# 18_Power_Management.net
KiCad netlist of a schematic drawn in Altium Designer
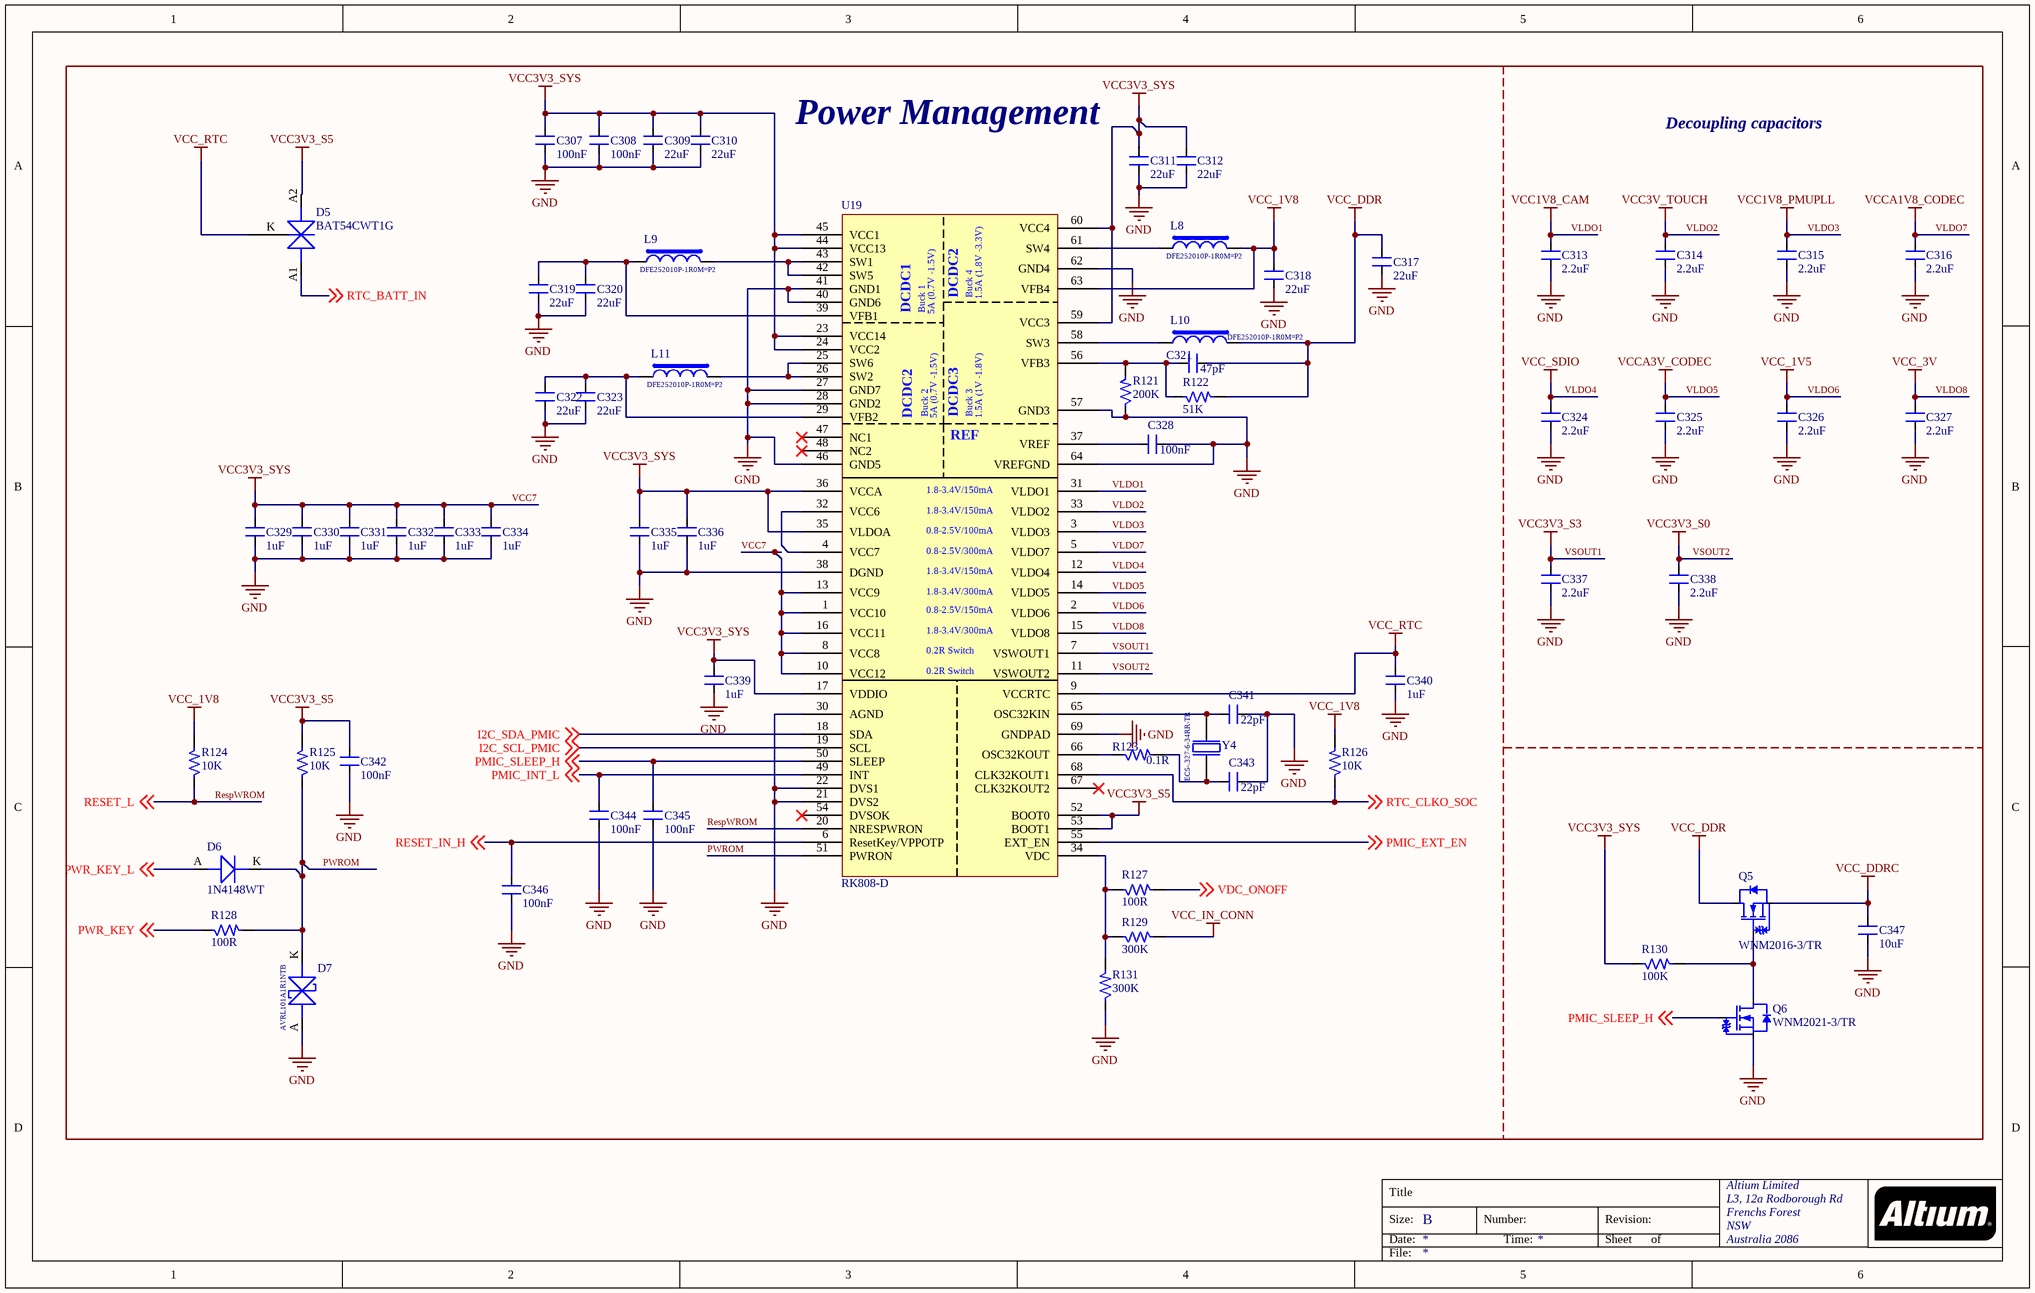
[diagram p0: [18] Power_Management.SchDoc]

(export (version "E")
  (design (tool "Eeschema 10.0.6"))
  (components
    (comp (ref "C307")
      (value "100nF")
      (footprint "CAP_0402")
      (description "0.1µF ±10% 25V Ceramic Capacitor X7R 0402 (1005 Metric)")
      (fields
        (field (name "MANUFACTURER") "Walsin Technology Corporation")
        (field (name "MANUFACTURER PART NUMBER") "0402B104K250CT")
      )
      (libsource (lib "EsteemPCB_SOM_Course_intlib") (part "CAP_100nF-25V-10%-0402"))
    )
    (comp (ref "C308")
      (value "100nF")
      (footprint "CAP_0402")
      (description "0.1µF ±10% 25V Ceramic Capacitor X7R 0402 (1005 Metric)")
      (fields
        (field (name "MANUFACTURER") "Walsin Technology Corporation")
        (field (name "MANUFACTURER PART NUMBER") "0402B104K250CT")
      )
      (libsource (lib "EsteemPCB_SOM_Course_intlib") (part "CAP_100nF-25V-10%-0402"))
    )
    (comp (ref "C309")
      (value "22uF")
      (footprint "CAP_0603")
      (description "22µF ±20% 10V Ceramic Capacitor X5R 0603 (1608 Metric)")
      (fields
        (field (name "MANUFACTURER") "Murata Electronics")
        (field (name "MANUFACTURER PART NUMBER") "GRM188R61A226ME15D")
      )
      (libsource (lib "EsteemPCB_SOM_Course_intlib") (part "CAP_22uF-10V-20%-0603"))
    )
    (comp (ref "C310")
      (value "22uF")
      (footprint "CAP_0603")
      (description "22µF ±20% 10V Ceramic Capacitor X5R 0603 (1608 Metric)")
      (fields
        (field (name "MANUFACTURER") "Murata Electronics")
        (field (name "MANUFACTURER PART NUMBER") "GRM188R61A226ME15D")
      )
      (libsource (lib "EsteemPCB_SOM_Course_intlib") (part "CAP_22uF-10V-20%-0603"))
    )
    (comp (ref "C311")
      (value "22uF")
      (footprint "CAP_0603")
      (description "22µF ±20% 10V Ceramic Capacitor X5R 0603 (1608 Metric)")
      (fields
        (field (name "MANUFACTURER") "Murata Electronics")
        (field (name "MANUFACTURER PART NUMBER") "GRM188R61A226ME15D")
      )
      (libsource (lib "EsteemPCB_SOM_Course_intlib") (part "CAP_22uF-10V-20%-0603"))
    )
    (comp (ref "C312")
      (value "22uF")
      (footprint "CAP_0603")
      (description "22µF ±20% 10V Ceramic Capacitor X5R 0603 (1608 Metric)")
      (fields
        (field (name "MANUFACTURER") "Murata Electronics")
        (field (name "MANUFACTURER PART NUMBER") "GRM188R61A226ME15D")
      )
      (libsource (lib "EsteemPCB_SOM_Course_intlib") (part "CAP_22uF-10V-20%-0603"))
    )
    (comp (ref "C313")
      (value "2.2uF")
      (footprint "CAP_0402")
      (description "2.2µF ±10% 10V Ceramic Capacitor X5R 0402 (1005 Metric)")
      (fields
        (field (name "MANUFACTURER") "Murata Electronics")
        (field (name "MANUFACTURER PART NUMBER") "GRM155R61A225KE95D")
      )
      (libsource (lib "EsteemPCB_SOM_Course_intlib") (part "CAP_2.2uF-10V-10%-0402"))
    )
    (comp (ref "C314")
      (value "2.2uF")
      (footprint "CAP_0402")
      (description "2.2µF ±10% 10V Ceramic Capacitor X5R 0402 (1005 Metric)")
      (fields
        (field (name "MANUFACTURER") "Murata Electronics")
        (field (name "MANUFACTURER PART NUMBER") "GRM155R61A225KE95D")
      )
      (libsource (lib "EsteemPCB_SOM_Course_intlib") (part "CAP_2.2uF-10V-10%-0402"))
    )
    (comp (ref "C315")
      (value "2.2uF")
      (footprint "CAP_0402")
      (description "2.2µF ±10% 10V Ceramic Capacitor X5R 0402 (1005 Metric)")
      (fields
        (field (name "MANUFACTURER") "Murata Electronics")
        (field (name "MANUFACTURER PART NUMBER") "GRM155R61A225KE95D")
      )
      (libsource (lib "EsteemPCB_SOM_Course_intlib") (part "CAP_2.2uF-10V-10%-0402"))
    )
    (comp (ref "C316")
      (value "2.2uF")
      (footprint "CAP_0402")
      (description "2.2µF ±10% 10V Ceramic Capacitor X5R 0402 (1005 Metric)")
      (fields
        (field (name "MANUFACTURER") "Murata Electronics")
        (field (name "MANUFACTURER PART NUMBER") "GRM155R61A225KE95D")
      )
      (libsource (lib "EsteemPCB_SOM_Course_intlib") (part "CAP_2.2uF-10V-10%-0402"))
    )
    (comp (ref "C317")
      (value "22uF")
      (footprint "CAP_0603")
      (description "22µF ±20% 10V Ceramic Capacitor X5R 0603 (1608 Metric)")
      (fields
        (field (name "MANUFACTURER") "Murata Electronics")
        (field (name "MANUFACTURER PART NUMBER") "GRM188R61A226ME15D")
      )
      (libsource (lib "EsteemPCB_SOM_Course_intlib") (part "CAP_22uF-10V-20%-0603"))
    )
    (comp (ref "C318")
      (value "22uF")
      (footprint "CAP_0603")
      (description "22µF ±20% 10V Ceramic Capacitor X5R 0603 (1608 Metric)")
      (fields
        (field (name "MANUFACTURER") "Murata Electronics")
        (field (name "MANUFACTURER PART NUMBER") "GRM188R61A226ME15D")
      )
      (libsource (lib "EsteemPCB_SOM_Course_intlib") (part "CAP_22uF-10V-20%-0603"))
    )
    (comp (ref "C319")
      (value "22uF")
      (footprint "CAP_0603")
      (description "22µF ±20% 10V Ceramic Capacitor X5R 0603 (1608 Metric)")
      (fields
        (field (name "MANUFACTURER") "Murata Electronics")
        (field (name "MANUFACTURER PART NUMBER") "GRM188R61A226ME15D")
      )
      (libsource (lib "EsteemPCB_SOM_Course_intlib") (part "CAP_22uF-10V-20%-0603"))
    )
    (comp (ref "C320")
      (value "22uF")
      (footprint "CAP_0603")
      (description "22µF ±20% 10V Ceramic Capacitor X5R 0603 (1608 Metric)")
      (fields
        (field (name "MANUFACTURER") "Murata Electronics")
        (field (name "MANUFACTURER PART NUMBER") "GRM188R61A226ME15D")
      )
      (libsource (lib "EsteemPCB_SOM_Course_intlib") (part "CAP_22uF-10V-20%-0603"))
    )
    (comp (ref "C321")
      (value "47pF")
      (footprint "CAP_0402")
      (description "47pF ±10% 10V Ceramic Capacitor C0G, NP0 0402 (1005 Metric)")
      (fields
        (field (name "MANUFACTURER") "KEMET")
        (field (name "MANUFACTURER PART NUMBER") "C0402C470K8GAC7867")
      )
      (libsource (lib "EsteemPCB_SOM_Course_intlib") (part "CAP_47pF-10V-10%-0402"))
    )
    (comp (ref "C322")
      (value "22uF")
      (footprint "CAP_0603")
      (description "22µF ±20% 10V Ceramic Capacitor X5R 0603 (1608 Metric)")
      (fields
        (field (name "MANUFACTURER") "Murata Electronics")
        (field (name "MANUFACTURER PART NUMBER") "GRM188R61A226ME15D")
      )
      (libsource (lib "EsteemPCB_SOM_Course_intlib") (part "CAP_22uF-10V-20%-0603"))
    )
    (comp (ref "C323")
      (value "22uF")
      (footprint "CAP_0603")
      (description "22µF ±20% 10V Ceramic Capacitor X5R 0603 (1608 Metric)")
      (fields
        (field (name "MANUFACTURER") "Murata Electronics")
        (field (name "MANUFACTURER PART NUMBER") "GRM188R61A226ME15D")
      )
      (libsource (lib "EsteemPCB_SOM_Course_intlib") (part "CAP_22uF-10V-20%-0603"))
    )
    (comp (ref "C324")
      (value "2.2uF")
      (footprint "CAP_0402")
      (description "2.2µF ±10% 10V Ceramic Capacitor X5R 0402 (1005 Metric)")
      (fields
        (field (name "MANUFACTURER") "Murata Electronics")
        (field (name "MANUFACTURER PART NUMBER") "GRM155R61A225KE95D")
      )
      (libsource (lib "EsteemPCB_SOM_Course_intlib") (part "CAP_2.2uF-10V-10%-0402"))
    )
    (comp (ref "C325")
      (value "2.2uF")
      (footprint "CAP_0402")
      (description "2.2µF ±10% 10V Ceramic Capacitor X5R 0402 (1005 Metric)")
      (fields
        (field (name "MANUFACTURER") "Murata Electronics")
        (field (name "MANUFACTURER PART NUMBER") "GRM155R61A225KE95D")
      )
      (libsource (lib "EsteemPCB_SOM_Course_intlib") (part "CAP_2.2uF-10V-10%-0402"))
    )
    (comp (ref "C326")
      (value "2.2uF")
      (footprint "CAP_0402")
      (description "2.2µF ±10% 10V Ceramic Capacitor X5R 0402 (1005 Metric)")
      (fields
        (field (name "MANUFACTURER") "Murata Electronics")
        (field (name "MANUFACTURER PART NUMBER") "GRM155R61A225KE95D")
      )
      (libsource (lib "EsteemPCB_SOM_Course_intlib") (part "CAP_2.2uF-10V-10%-0402"))
    )
    (comp (ref "C327")
      (value "2.2uF")
      (footprint "CAP_0402")
      (description "2.2µF ±10% 10V Ceramic Capacitor X5R 0402 (1005 Metric)")
      (fields
        (field (name "MANUFACTURER") "Murata Electronics")
        (field (name "MANUFACTURER PART NUMBER") "GRM155R61A225KE95D")
      )
      (libsource (lib "EsteemPCB_SOM_Course_intlib") (part "CAP_2.2uF-10V-10%-0402"))
    )
    (comp (ref "C328")
      (value "100nF")
      (footprint "CAP_0402")
      (description "0.1µF ±10% 10V Ceramic Capacitor X7R 0402 (1005 Metric)")
      (fields
        (field (name "MANUFACTURER") "Yageo")
        (field (name "MANUFACTURER PART NUMBER") "CC0402KRX7R6BB104")
      )
      (libsource (lib "EsteemPCB_SOM_Course_intlib") (part "CAP_100nF-10V-10%-0402"))
    )
    (comp (ref "C329")
      (value "1uF")
      (footprint "CAP_0402")
      (description "1µF ±10% 10V Ceramic Capacitor X6S 0402 (1005 Metric)")
      (fields
        (field (name "MANUFACTURER") "Murata Electronics")
        (field (name "MANUFACTURER PART NUMBER") "GRT155C81A105KE01D")
      )
      (libsource (lib "EsteemPCB_SOM_Course_intlib") (part "CAP_1uF-10V-10%-0402"))
    )
    (comp (ref "C330")
      (value "1uF")
      (footprint "CAP_0402")
      (description "1µF ±10% 10V Ceramic Capacitor X6S 0402 (1005 Metric)")
      (fields
        (field (name "MANUFACTURER") "Murata Electronics")
        (field (name "MANUFACTURER PART NUMBER") "GRT155C81A105KE01D")
      )
      (libsource (lib "EsteemPCB_SOM_Course_intlib") (part "CAP_1uF-10V-10%-0402"))
    )
    (comp (ref "C331")
      (value "1uF")
      (footprint "CAP_0402")
      (description "1µF ±10% 10V Ceramic Capacitor X6S 0402 (1005 Metric)")
      (fields
        (field (name "MANUFACTURER") "Murata Electronics")
        (field (name "MANUFACTURER PART NUMBER") "GRT155C81A105KE01D")
      )
      (libsource (lib "EsteemPCB_SOM_Course_intlib") (part "CAP_1uF-10V-10%-0402"))
    )
    (comp (ref "C332")
      (value "1uF")
      (footprint "CAP_0402")
      (description "1µF ±10% 10V Ceramic Capacitor X6S 0402 (1005 Metric)")
      (fields
        (field (name "MANUFACTURER") "Murata Electronics")
        (field (name "MANUFACTURER PART NUMBER") "GRT155C81A105KE01D")
      )
      (libsource (lib "EsteemPCB_SOM_Course_intlib") (part "CAP_1uF-10V-10%-0402"))
    )
    (comp (ref "C333")
      (value "1uF")
      (footprint "CAP_0402")
      (description "1µF ±10% 10V Ceramic Capacitor X6S 0402 (1005 Metric)")
      (fields
        (field (name "MANUFACTURER") "Murata Electronics")
        (field (name "MANUFACTURER PART NUMBER") "GRT155C81A105KE01D")
      )
      (libsource (lib "EsteemPCB_SOM_Course_intlib") (part "CAP_1uF-10V-10%-0402"))
    )
    (comp (ref "C334")
      (value "1uF")
      (footprint "CAP_0402")
      (description "1µF ±10% 10V Ceramic Capacitor X6S 0402 (1005 Metric)")
      (fields
        (field (name "MANUFACTURER") "Murata Electronics")
        (field (name "MANUFACTURER PART NUMBER") "GRT155C81A105KE01D")
      )
      (libsource (lib "EsteemPCB_SOM_Course_intlib") (part "CAP_1uF-10V-10%-0402"))
    )
    (comp (ref "C335")
      (value "1uF")
      (footprint "CAP_0402")
      (description "1µF ±10% 10V Ceramic Capacitor X6S 0402 (1005 Metric)")
      (fields
        (field (name "MANUFACTURER") "Murata Electronics")
        (field (name "MANUFACTURER PART NUMBER") "GRT155C81A105KE01D")
      )
      (libsource (lib "EsteemPCB_SOM_Course_intlib") (part "CAP_1uF-10V-10%-0402"))
    )
    (comp (ref "C336")
      (value "1uF")
      (footprint "CAP_0402")
      (description "1µF ±10% 10V Ceramic Capacitor X6S 0402 (1005 Metric)")
      (fields
        (field (name "MANUFACTURER") "Murata Electronics")
        (field (name "MANUFACTURER PART NUMBER") "GRT155C81A105KE01D")
      )
      (libsource (lib "EsteemPCB_SOM_Course_intlib") (part "CAP_1uF-10V-10%-0402"))
    )
    (comp (ref "C337")
      (value "2.2uF")
      (footprint "CAP_0402")
      (description "2.2µF ±10% 10V Ceramic Capacitor X5R 0402 (1005 Metric)")
      (fields
        (field (name "MANUFACTURER") "Murata Electronics")
        (field (name "MANUFACTURER PART NUMBER") "GRM155R61A225KE95D")
      )
      (libsource (lib "EsteemPCB_SOM_Course_intlib") (part "CAP_2.2uF-10V-10%-0402"))
    )
    (comp (ref "C338")
      (value "2.2uF")
      (footprint "CAP_0402")
      (description "2.2µF ±10% 10V Ceramic Capacitor X5R 0402 (1005 Metric)")
      (fields
        (field (name "MANUFACTURER") "Murata Electronics")
        (field (name "MANUFACTURER PART NUMBER") "GRM155R61A225KE95D")
      )
      (libsource (lib "EsteemPCB_SOM_Course_intlib") (part "CAP_2.2uF-10V-10%-0402"))
    )
    (comp (ref "C339")
      (value "1uF")
      (footprint "CAP_0402")
      (description "1µF ±10% 10V Ceramic Capacitor X6S 0402 (1005 Metric)")
      (fields
        (field (name "MANUFACTURER") "Murata Electronics")
        (field (name "MANUFACTURER PART NUMBER") "GRT155C81A105KE01D")
      )
      (libsource (lib "EsteemPCB_SOM_Course_intlib") (part "CAP_1uF-10V-10%-0402"))
    )
    (comp (ref "C340")
      (value "1uF")
      (footprint "CAP_0402")
      (description "1µF ±10% 16V Ceramic Capacitor X5R 0402 (1005 Metric)")
      (fields
        (field (name "MANUFACTURER") "Knowles Novacap")
        (field (name "MANUFACTURER PART NUMBER") "0402BW105K160YT")
      )
      (libsource (lib "EsteemPCB_SOM_Course_intlib") (part "CAP_1uF-16V-10%-0402"))
    )
    (comp (ref "C341")
      (value "22pF")
      (footprint "CAP_0402")
      (description "22pF ±10% 10V Ceramic Capacitor C0G, NP0 0402 (1005 Metric)")
      (fields
        (field (name "MANUFACTURER") "KEMET")
        (field (name "MANUFACTURER PART NUMBER") "C0402C220K8GACTU")
      )
      (libsource (lib "EsteemPCB_SOM_Course_intlib") (part "CAP_22pF-10V-10%-0402"))
    )
    (comp (ref "C342")
      (value "100nF")
      (footprint "CAP_0402")
      (description "0.1µF ±10% 10V Ceramic Capacitor X7R 0402 (1005 Metric)")
      (fields
        (field (name "MANUFACTURER") "Yageo")
        (field (name "MANUFACTURER PART NUMBER") "CC0402KRX7R6BB104")
      )
      (libsource (lib "EsteemPCB_SOM_Course_intlib") (part "CAP_100nF-10V-10%-0402"))
    )
    (comp (ref "C343")
      (value "22pF")
      (footprint "CAP_0402")
      (description "22pF ±10% 10V Ceramic Capacitor C0G, NP0 0402 (1005 Metric)")
      (fields
        (field (name "MANUFACTURER") "KEMET")
        (field (name "MANUFACTURER PART NUMBER") "C0402C220K8GACTU")
      )
      (libsource (lib "EsteemPCB_SOM_Course_intlib") (part "CAP_22pF-10V-10%-0402"))
    )
    (comp (ref "C344")
      (value "100nF")
      (footprint "CAP_0402")
      (description "0.1µF ±10% 10V Ceramic Capacitor X7R 0402 (1005 Metric)")
      (fields
        (field (name "MANUFACTURER") "Yageo")
        (field (name "MANUFACTURER PART NUMBER") "CC0402KRX7R6BB104")
      )
      (libsource (lib "EsteemPCB_SOM_Course_intlib") (part "CAP_100nF-10V-10%-0402"))
    )
    (comp (ref "C345")
      (value "100nF")
      (footprint "CAP_0402")
      (description "0.1µF ±10% 10V Ceramic Capacitor X7R 0402 (1005 Metric)")
      (fields
        (field (name "MANUFACTURER") "Yageo")
        (field (name "MANUFACTURER PART NUMBER") "CC0402KRX7R6BB104")
      )
      (libsource (lib "EsteemPCB_SOM_Course_intlib") (part "CAP_100nF-10V-10%-0402"))
    )
    (comp (ref "C346")
      (value "100nF")
      (footprint "CAP_0402")
      (description "0.1µF ±10% 10V Ceramic Capacitor X7R 0402 (1005 Metric)")
      (fields
        (field (name "MANUFACTURER") "Yageo")
        (field (name "MANUFACTURER PART NUMBER") "CC0402KRX7R6BB104")
      )
      (libsource (lib "EsteemPCB_SOM_Course_intlib") (part "CAP_100nF-10V-10%-0402"))
    )
    (comp (ref "C347")
      (value "10uF")
      (footprint "CAP_0402")
      (description "10µF ±20% 10V Ceramic Capacitor X5R 0402 (1005 Metric)")
      (fields
        (field (name "MANUFACTURER PART NUMBER") "CL05A106MP5NUNC")
        (field (name "MANUFACTURER") "Samsung Electro-Mechanics")
      )
      (libsource (lib "EsteemPCB_SOM_Course_intlib") (part "CAP_10uF-10V-20%-0402"))
    )
    (comp (ref "D5")
      (value "BAT54CWT1G")
      (footprint "DIO_SOT-323-3")
      (description "Diode Array 1 Pair Common Cathode Schottky 30V 200mA (DC) Surface Mount SC-70, SOT-323")
      (fields (field (name "MANUFACTURER") "ON Semiconductor"))
      (libsource (lib "EsteemPCB_SOM_Course_intlib") (part "DIO-S-A_30V-200mA-SOT-323"))
    )
    (comp (ref "D6")
      (value "1N4148WT")
      (footprint "DIO_SOD523")
      (description "Diode Standard 100V 300mA (DC) Surface Mount SOD-123")
      (fields (field (name "MANUFACTURER") "FAIRCHILD"))
      (libsource (lib "EsteemPCB_SOM_Course_intlib") (part "DIO_75V-200mA-SOD-523F"))
    )
    (comp (ref "D7")
      (value "AVRL101A1R1NTB")
      (footprint "DIO_0402_SMD")
      (description "39V Varistor 1 Circuit Surface Mount, MLCV 0402 (1005 Metric)")
      (fields (field (name "MANUFACTURER") "TDK Corporation"))
      (libsource (lib "EsteemPCB_SOM_Course_intlib") (part "DIO-T_10V-39V-0402"))
    )
    (comp (ref "L8")
      (value "DFE252010P-1R0M=P2")
      (footprint "IND_1008")
      (description "1µH Shielded Wirewound Inductor 3.8A 54mOhm Max 1008 (2520 Metric)")
      (fields (field (name "MANUFACTURER") "Murata Electronics"))
      (libsource (lib "EsteemPCB_SOM_Course_intlib") (part "IND_1uH-3.8A-20%-1008"))
    )
    (comp (ref "L9")
      (value "DFE252010P-1R0M=P2")
      (footprint "IND_1008")
      (description "1µH Shielded Wirewound Inductor 3.8A 54mOhm Max 1008 (2520 Metric)")
      (fields (field (name "MANUFACTURER") "Murata Electronics"))
      (libsource (lib "EsteemPCB_SOM_Course_intlib") (part "IND_1uH-3.8A-20%-1008"))
    )
    (comp (ref "L10")
      (value "DFE252010P-1R0M=P2")
      (footprint "IND_1008")
      (description "1µH Shielded Wirewound Inductor 3.8A 54mOhm Max 1008 (2520 Metric)")
      (fields (field (name "MANUFACTURER") "Murata Electronics"))
      (libsource (lib "EsteemPCB_SOM_Course_intlib") (part "IND_1uH-3.8A-20%-1008"))
    )
    (comp (ref "L11")
      (value "DFE252010P-1R0M=P2")
      (footprint "IND_1008")
      (description "1µH Shielded Wirewound Inductor 3.8A 54mOhm Max 1008 (2520 Metric)")
      (fields (field (name "MANUFACTURER") "Murata Electronics"))
      (libsource (lib "EsteemPCB_SOM_Course_intlib") (part "IND_1uH-3.8A-20%-1008"))
    )
    (comp (ref "Q5")
      (value "WNM2016-3/TR")
      (footprint "SOT 23-3")
      (description "N Channel 20V 2.9A 1V @ 250uA 47mΩ @ 3.6A,4.5V 700mW SOT-23(SOT-23-3) MOSFET RoHS")
      (fields (field (name "MANUFACTURER") "WILLSEMI(Will Semicon)"))
      (libsource (lib "EsteemPCB_SOM_Course_intlib") (part "MOSFET-N_20V-2.9A-SOT-23"))
    )
    (comp (ref "Q6")
      (value "WNM2021-3/TR")
      (footprint "SOT-323-3")
      (description "N Channel 20V 820mA 850mV @ 250uA 310mΩ @ 550mA,4.5V 310mW SOT-323(SC-70) MOSFET RoHS")
      (fields (field (name "MANUFACTURER") "WILLSEMI(Will Semicon)"))
      (libsource (lib "EsteemPCB_SOM_Course_intlib") (part "MOSFET-N_20V-820mA-SOT-323"))
    )
    (comp (ref "R121")
      (value "200K")
      (footprint "RES_0402")
      (description "200 kOhms ±1% 0.1W, 1/10W Chip Resistor 0402 (1005 Metric) Automotive AEC-Q200 Thick Film")
      (fields
        (field (name "MANUFACTURER") "Panasonic Electronic Components")
        (field (name "MANUFACTURER PART NUMBER") "ERJ-2RKF2003X")
      )
      (libsource (lib "EsteemPCB_SOM_Course_intlib") (part "RES_200K-0.1W-1%-0402"))
    )
    (comp (ref "R122")
      (value "51K")
      (footprint "RES_0402")
      (description "51 kOhms ±1% 0.1W, 1/10W Chip Resistor 0402 (1005 Metric) Automotive AEC-Q200 Thick Film")
      (fields
        (field (name "MANUFACTURER") "Panasonic Electronic Components")
        (field (name "MANUFACTURER PART NUMBER") "ERJ-2RKF5102X")
      )
      (libsource (lib "EsteemPCB_SOM_Course_intlib") (part "RES_51K-0.1W-1%-0402"))
    )
    (comp (ref "R123")
      (value "0.1R")
      (footprint "RES_0402")
      (fields
        (field (name "MANUFACTURER") "Samsung Electro-Mechanics")
        (field (name "MANUFACTURER PART NUMBER") "RUT1005FR100CS")
      )
      (libsource (lib "EsteemPCB_SOM_Course_intlib") (part "RES_0.1R-0.1W-1%-0402"))
    )
    (comp (ref "R124")
      (value "10K")
      (footprint "RES_0402")
      (description "10 kOhms ±1% 0.1W, 1/10W Chip Resistor 0402 (1005 Metric) Anti-Sulfur Thin Film")
      (fields
        (field (name "MANUFACTURER") "Vishay Beyschlag/Draloric/BC Components")
        (field (name "MANUFACTURER PART NUMBER") "MCS04020C1002FE000")
      )
      (libsource (lib "EsteemPCB_SOM_Course_intlib") (part "RES_10K-0.1W-1%-0402"))
    )
    (comp (ref "R125")
      (value "10K")
      (footprint "RES_0402")
      (description "10 kOhms ±1% 0.1W, 1/10W Chip Resistor 0402 (1005 Metric) Anti-Sulfur Thin Film")
      (fields
        (field (name "MANUFACTURER") "Vishay Beyschlag/Draloric/BC Components")
        (field (name "MANUFACTURER PART NUMBER") "MCS04020C1002FE000")
      )
      (libsource (lib "EsteemPCB_SOM_Course_intlib") (part "RES_10K-0.1W-1%-0402"))
    )
    (comp (ref "R126")
      (value "10K")
      (footprint "RES_0402")
      (description "10 kOhms ±1% 0.1W, 1/10W Chip Resistor 0402 (1005 Metric) Anti-Sulfur Thin Film")
      (fields
        (field (name "MANUFACTURER") "Vishay Beyschlag/Draloric/BC Components")
        (field (name "MANUFACTURER PART NUMBER") "MCS04020C1002FE000")
      )
      (libsource (lib "EsteemPCB_SOM_Course_intlib") (part "RES_10K-0.1W-1%-0402"))
    )
    (comp (ref "R127")
      (value "100R")
      (footprint "RES_0402")
      (fields
        (field (name "MANUFACTURER") "KOA Speer Electronics, Inc.")
        (field (name "MANUFACTURER PART NUMBER") "RK73H1ETTP1000F")
      )
      (libsource (lib "EsteemPCB_SOM_Course_intlib") (part "RES_100R-0.1W-1%-0402"))
    )
    (comp (ref "R128")
      (value "100R")
      (footprint "RES_0402")
      (fields
        (field (name "MANUFACTURER") "KOA Speer Electronics, Inc.")
        (field (name "MANUFACTURER PART NUMBER") "RK73H1ETTP1000F")
      )
      (libsource (lib "EsteemPCB_SOM_Course_intlib") (part "RES_100R-0.1W-1%-0402"))
    )
    (comp (ref "R129")
      (value "300K")
      (footprint "RES_0402")
      (description "300 kOhms ±1% 0.1W, 1/10W Chip Resistor 0402 (1005 Metric) Automotive AEC-Q200 Thick Film")
      (fields
        (field (name "MANUFACTURER") "Panasonic Electronic Components")
        (field (name "MANUFACTURER PART NUMBER") "ERJ-2RKF3003X")
      )
      (libsource (lib "EsteemPCB_SOM_Course_intlib") (part "RES_300K-0.1W-1%-0402"))
    )
    (comp (ref "R130")
      (value "100K")
      (footprint "RES_0402")
      (description "100 kOhms ±1% 0.1W, 1/10W Chip Resistor 0402 (1005 Metric) Anti-Sulfur Thin Film")
      (fields
        (field (name "MANUFACTURER") "Vishay Beyschlag/Draloric/BC Components")
        (field (name "MANUFACTURER PART NUMBER") "MCS04020C1003FE000")
      )
      (libsource (lib "EsteemPCB_SOM_Course_intlib") (part "RES_100K-0.1W-1%-0402"))
    )
    (comp (ref "R131")
      (value "300K")
      (footprint "RES_0402")
      (description "300 kOhms ±1% 0.1W, 1/10W Chip Resistor 0402 (1005 Metric) Automotive AEC-Q200 Thick Film")
      (fields
        (field (name "MANUFACTURER") "Panasonic Electronic Components")
        (field (name "MANUFACTURER PART NUMBER") "ERJ-2RKF3003X")
      )
      (libsource (lib "EsteemPCB_SOM_Course_intlib") (part "RES_300K-0.1W-1%-0402"))
    )
    (comp (ref "U19")
      (value "RK808-D")
      (footprint "QFN68_13.7_220.4X220.4_SMD")
      (description "The RK808 is a complete power supply solution for Portable systems.")
      (fields (field (name "MANUFACTURER") "Rockchip"))
      (libsource (lib "EsteemPCB_SOM_Course_intlib") (part "IC_RK808-D-QFN68"))
    )
    (comp (ref "Y4")
      (value "ECS-.327-6-34RR-TR")
      (footprint "XTAL_ECS-.327-6-34RR-TR")
      (description "32.768kHz ±20ppm Crystal 12pF 80 kOhms 2-SMD, No Lead")
      (fields (field (name "MANUFACTURER") "Ecliptek"))
      (libsource (lib "EsteemPCB_SOM_Course_intlib") (part "XTAL_32.768Khz-22pF-SMD"))
    )
  )
  (nets
    (net (code "1") (name "/PWROM") (class "Default")
      (node (ref "D6") (pin "K") (pinfunction "CATHODE_K") (pintype "passive"))
      (node (ref "D7") (pin "K") (pinfunction "K_K") (pintype "passive"))
      (node (ref "R125") (pin "1") (pinfunction "1_1") (pintype "passive"))
      (node (ref "R128") (pin "2") (pinfunction "2_2") (pintype "passive"))
      (node (ref "U19") (pin "51") (pinfunction "PWRON_51") (pintype "passive"))
    )
    (net (code "2") (name "GND") (class "Default")
      (node (ref "C307") (pin "1") (pinfunction "1_1") (pintype "passive"))
      (node (ref "C308") (pin "1") (pinfunction "1_1") (pintype "passive"))
      (node (ref "C309") (pin "1") (pinfunction "1_1") (pintype "passive"))
      (node (ref "C310") (pin "1") (pinfunction "1_1") (pintype "passive"))
      (node (ref "C311") (pin "1") (pinfunction "1_1") (pintype "passive"))
      (node (ref "C312") (pin "1") (pinfunction "1_1") (pintype "passive"))
      (node (ref "C313") (pin "1") (pinfunction "1_1") (pintype "passive"))
      (node (ref "C314") (pin "1") (pinfunction "1_1") (pintype "passive"))
      (node (ref "C315") (pin "1") (pinfunction "1_1") (pintype "passive"))
      (node (ref "C316") (pin "1") (pinfunction "1_1") (pintype "passive"))
      (node (ref "C317") (pin "1") (pinfunction "1_1") (pintype "passive"))
      (node (ref "C318") (pin "1") (pinfunction "1_1") (pintype "passive"))
      (node (ref "C319") (pin "1") (pinfunction "1_1") (pintype "passive"))
      (node (ref "C320") (pin "1") (pinfunction "1_1") (pintype "passive"))
      (node (ref "C322") (pin "1") (pinfunction "1_1") (pintype "passive"))
      (node (ref "C323") (pin "1") (pinfunction "1_1") (pintype "passive"))
      (node (ref "C324") (pin "1") (pinfunction "1_1") (pintype "passive"))
      (node (ref "C325") (pin "1") (pinfunction "1_1") (pintype "passive"))
      (node (ref "C326") (pin "1") (pinfunction "1_1") (pintype "passive"))
      (node (ref "C327") (pin "1") (pinfunction "1_1") (pintype "passive"))
      (node (ref "C328") (pin "2") (pinfunction "2_2") (pintype "passive"))
      (node (ref "C329") (pin "1") (pinfunction "1_1") (pintype "passive"))
      (node (ref "C330") (pin "1") (pinfunction "1_1") (pintype "passive"))
      (node (ref "C331") (pin "1") (pinfunction "1_1") (pintype "passive"))
      (node (ref "C332") (pin "1") (pinfunction "1_1") (pintype "passive"))
      (node (ref "C333") (pin "1") (pinfunction "1_1") (pintype "passive"))
      (node (ref "C334") (pin "1") (pinfunction "1_1") (pintype "passive"))
      (node (ref "C335") (pin "1") (pinfunction "1_1") (pintype "passive"))
      (node (ref "C336") (pin "1") (pinfunction "1_1") (pintype "passive"))
      (node (ref "C337") (pin "1") (pinfunction "1_1") (pintype "passive"))
      (node (ref "C338") (pin "1") (pinfunction "1_1") (pintype "passive"))
      (node (ref "C339") (pin "1") (pinfunction "1_1") (pintype "passive"))
      (node (ref "C340") (pin "1") (pinfunction "1_1") (pintype "passive"))
      (node (ref "C341") (pin "2") (pinfunction "2_2") (pintype "passive"))
      (node (ref "C342") (pin "1") (pinfunction "1_1") (pintype "passive"))
      (node (ref "C343") (pin "2") (pinfunction "2_2") (pintype "passive"))
      (node (ref "C344") (pin "1") (pinfunction "1_1") (pintype "passive"))
      (node (ref "C345") (pin "1") (pinfunction "1_1") (pintype "passive"))
      (node (ref "C346") (pin "1") (pinfunction "1_1") (pintype "passive"))
      (node (ref "C347") (pin "1") (pinfunction "1_1") (pintype "passive"))
      (node (ref "D7") (pin "A") (pinfunction "A_A") (pintype "passive"))
      (node (ref "Q6") (pin "2") (pinfunction "S_2") (pintype "passive"))
      (node (ref "R121") (pin "1") (pinfunction "1_1") (pintype "passive"))
      (node (ref "R131") (pin "1") (pinfunction "1_1") (pintype "passive"))
      (node (ref "U19") (pin "21") (pinfunction "DVS2_21") (pintype "passive"))
      (node (ref "U19") (pin "22") (pinfunction "DVS1_22") (pintype "passive"))
      (node (ref "U19") (pin "27") (pinfunction "GND7_27") (pintype "passive"))
      (node (ref "U19") (pin "28") (pinfunction "GND2_28") (pintype "passive"))
      (node (ref "U19") (pin "30") (pinfunction "AGND_30") (pintype "passive"))
      (node (ref "U19") (pin "38") (pinfunction "DGND_38") (pintype "passive"))
      (node (ref "U19") (pin "40") (pinfunction "GND6_40") (pintype "passive"))
      (node (ref "U19") (pin "41") (pinfunction "GND1_41") (pintype "passive"))
      (node (ref "U19") (pin "46") (pinfunction "GND5_46") (pintype "passive"))
      (node (ref "U19") (pin "57") (pinfunction "GND3_57") (pintype "passive"))
      (node (ref "U19") (pin "62") (pinfunction "GND4_62") (pintype "passive"))
      (node (ref "U19") (pin "64") (pinfunction "VREFGND_64") (pintype "passive"))
      (node (ref "U19") (pin "69") (pinfunction "GNDPAD_69") (pintype "passive"))
    )
    (net (code "3") (name "I2C_SCL_PMIC") (class "Default")
      (node (ref "U19") (pin "19") (pinfunction "SCL_19") (pintype "passive"))
    )
    (net (code "4") (name "I2C_SDA_PMIC") (class "Default")
      (node (ref "U19") (pin "18") (pinfunction "SDA_18") (pintype "passive"))
    )
    (net (code "5") (name "Net-(C343-Pad1)") (class "Default")
      (node (ref "C343") (pin "1") (pinfunction "1_1") (pintype "passive"))
      (node (ref "R123") (pin "2") (pinfunction "2_2") (pintype "passive"))
      (node (ref "Y4") (pin "1") (pinfunction "1_1") (pintype "passive"))
    )
    (net (code "6") (name "Net-(Q5-G)") (class "Default")
      (node (ref "Q5") (pin "1") (pinfunction "G_1") (pintype "passive"))
      (node (ref "Q6") (pin "3") (pinfunction "D_3") (pintype "passive"))
      (node (ref "R130") (pin "2") (pinfunction "2_2") (pintype "passive"))
    )
    (net (code "7") (name "Net-(U19-OSC32KIN)") (class "Default")
      (node (ref "C341") (pin "1") (pinfunction "1_1") (pintype "passive"))
      (node (ref "U19") (pin "65") (pinfunction "OSC32KIN_65") (pintype "passive"))
      (node (ref "Y4") (pin "2") (pinfunction "2_2") (pintype "passive"))
    )
    (net (code "8") (name "Net-(U19-OSC32KOUT)") (class "Default")
      (node (ref "R123") (pin "1") (pinfunction "1_1") (pintype "passive"))
      (node (ref "U19") (pin "66") (pinfunction "OSC32KOUT_66") (pintype "passive"))
    )
    (net (code "9") (name "Net-(U19-SW1)") (class "Default")
      (node (ref "L9") (pin "2") (pinfunction "2_2") (pintype "passive"))
      (node (ref "U19") (pin "42") (pinfunction "SW5_42") (pintype "passive"))
      (node (ref "U19") (pin "43") (pinfunction "SW1_43") (pintype "passive"))
    )
    (net (code "10") (name "Net-(U19-SW2)") (class "Default")
      (node (ref "L11") (pin "2") (pinfunction "2_2") (pintype "passive"))
      (node (ref "U19") (pin "25") (pinfunction "SW6_25") (pintype "passive"))
      (node (ref "U19") (pin "26") (pinfunction "SW2_26") (pintype "passive"))
    )
    (net (code "11") (name "Net-(U19-SW3)") (class "Default")
      (node (ref "L10") (pin "1") (pinfunction "1_1") (pintype "passive"))
      (node (ref "U19") (pin "58") (pinfunction "SW3_58") (pintype "passive"))
    )
    (net (code "12") (name "Net-(U19-SW4)") (class "Default")
      (node (ref "L8") (pin "1") (pinfunction "1_1") (pintype "passive"))
      (node (ref "U19") (pin "61") (pinfunction "SW4_61") (pintype "passive"))
    )
    (net (code "13") (name "Net-(U19-VCC6)") (class "Default")
      (node (ref "U19") (pin "32") (pinfunction "VCC6_32") (pintype "passive"))
      (node (ref "U19") (pin "4") (pinfunction "VCC7_4") (pintype "passive"))
    )
    (net (code "14") (name "Net-(U19-VDC)") (class "Default")
      (node (ref "R127") (pin "1") (pinfunction "1_1") (pintype "passive"))
      (node (ref "R129") (pin "1") (pinfunction "1_1") (pintype "passive"))
      (node (ref "R131") (pin "2") (pinfunction "2_2") (pintype "passive"))
      (node (ref "U19") (pin "34") (pinfunction "VDC_34") (pintype "passive"))
    )
    (net (code "15") (name "Net-(U19-VFB1)") (class "Default")
      (node (ref "C319") (pin "2") (pinfunction "2_2") (pintype "passive"))
      (node (ref "C320") (pin "2") (pinfunction "2_2") (pintype "passive"))
      (node (ref "L9") (pin "1") (pinfunction "1_1") (pintype "passive"))
      (node (ref "U19") (pin "39") (pinfunction "VFB1_39") (pintype "passive"))
    )
    (net (code "16") (name "Net-(U19-VFB2)") (class "Default")
      (node (ref "C322") (pin "2") (pinfunction "2_2") (pintype "passive"))
      (node (ref "C323") (pin "2") (pinfunction "2_2") (pintype "passive"))
      (node (ref "L11") (pin "1") (pinfunction "1_1") (pintype "passive"))
      (node (ref "U19") (pin "29") (pinfunction "VFB2_29") (pintype "passive"))
    )
    (net (code "17") (name "Net-(U19-VFB3)") (class "Default")
      (node (ref "C321") (pin "1") (pinfunction "1_1") (pintype "passive"))
      (node (ref "R121") (pin "2") (pinfunction "2_2") (pintype "passive"))
      (node (ref "R122") (pin "1") (pinfunction "1_1") (pintype "passive"))
      (node (ref "U19") (pin "56") (pinfunction "VFB3_56") (pintype "passive"))
    )
    (net (code "18") (name "Net-(U19-VREF)") (class "Default")
      (node (ref "C328") (pin "1") (pinfunction "1_1") (pintype "passive"))
      (node (ref "U19") (pin "37") (pinfunction "VREF_37") (pintype "passive"))
    )
    (net (code "19") (name "PMIC_EXT_EN") (class "Default")
      (node (ref "U19") (pin "55") (pinfunction "EXT_EN_55") (pintype "passive"))
    )
    (net (code "20") (name "PMIC_INT_L") (class "Default")
      (node (ref "C344") (pin "2") (pinfunction "2_2") (pintype "passive"))
      (node (ref "U19") (pin "49") (pinfunction "INT_49") (pintype "passive"))
    )
    (net (code "21") (name "PMIC_SLEEP_H") (class "Default")
      (node (ref "C345") (pin "2") (pinfunction "2_2") (pintype "passive"))
      (node (ref "Q6") (pin "1") (pinfunction "G_1") (pintype "passive"))
      (node (ref "U19") (pin "50") (pinfunction "SLEEP_50") (pintype "passive"))
    )
    (net (code "22") (name "PWR_KEY") (class "Default")
      (node (ref "R128") (pin "1") (pinfunction "1_1") (pintype "passive"))
    )
    (net (code "23") (name "PWR_KEY_L") (class "Default")
      (node (ref "D6") (pin "A") (pinfunction "ANODE_A") (pintype "passive"))
    )
    (net (code "24") (name "RESET_IN_H") (class "Default")
      (node (ref "C346") (pin "2") (pinfunction "2_2") (pintype "passive"))
      (node (ref "U19") (pin "6") (pinfunction "ResetKey/VPPOTP_6") (pintype "passive"))
    )
    (net (code "25") (name "RESET_L") (class "Default")
      (node (ref "R124") (pin "1") (pinfunction "1_1") (pintype "passive"))
      (node (ref "U19") (pin "20") (pinfunction "NRESPWRON_20") (pintype "passive"))
    )
    (net (code "26") (name "RTC_BATT_IN") (class "Default")
      (node (ref "D5") (pin "A1") (pinfunction "A1_A1") (pintype "passive"))
    )
    (net (code "27") (name "RTC_CLKO_SOC") (class "Default")
      (node (ref "R126") (pin "1") (pinfunction "1_1") (pintype "passive"))
      (node (ref "U19") (pin "68") (pinfunction "CLK32KOUT1_68") (pintype "passive"))
    )
    (net (code "28") (name "VCC1V8_CAM") (class "Default")
      (node (ref "C313") (pin "2") (pinfunction "2_2") (pintype "passive"))
      (node (ref "U19") (pin "31") (pinfunction "VLDO1_31") (pintype "passive"))
    )
    (net (code "29") (name "VCC1V8_PMUPLL") (class "Default")
      (node (ref "C315") (pin "2") (pinfunction "2_2") (pintype "passive"))
      (node (ref "U19") (pin "3") (pinfunction "VLDO3_3") (pintype "passive"))
    )
    (net (code "30") (name "VCC3V3_S0") (class "Default")
      (node (ref "C338") (pin "2") (pinfunction "2_2") (pintype "passive"))
      (node (ref "U19") (pin "11") (pinfunction "VSWOUT2_11") (pintype "passive"))
    )
    (net (code "31") (name "VCC3V3_S3") (class "Default")
      (node (ref "C337") (pin "2") (pinfunction "2_2") (pintype "passive"))
      (node (ref "U19") (pin "7") (pinfunction "VSWOUT1_7") (pintype "passive"))
    )
    (net (code "32") (name "VCC3V3_S5") (class "Default")
      (node (ref "C342") (pin "2") (pinfunction "2_2") (pintype "passive"))
      (node (ref "D5") (pin "A2") (pinfunction "A2_A2") (pintype "passive"))
      (node (ref "R125") (pin "2") (pinfunction "2_2") (pintype "passive"))
      (node (ref "U19") (pin "52") (pinfunction "BOOT0_52") (pintype "passive"))
      (node (ref "U19") (pin "53") (pinfunction "BOOT1_53") (pintype "passive"))
    )
    (net (code "33") (name "VCC3V3_SYS") (class "Default")
      (node (ref "C307") (pin "2") (pinfunction "2_2") (pintype "passive"))
      (node (ref "C308") (pin "2") (pinfunction "2_2") (pintype "passive"))
      (node (ref "C309") (pin "2") (pinfunction "2_2") (pintype "passive"))
      (node (ref "C310") (pin "2") (pinfunction "2_2") (pintype "passive"))
      (node (ref "C311") (pin "2") (pinfunction "2_2") (pintype "passive"))
      (node (ref "C312") (pin "2") (pinfunction "2_2") (pintype "passive"))
      (node (ref "C329") (pin "2") (pinfunction "2_2") (pintype "passive"))
      (node (ref "C330") (pin "2") (pinfunction "2_2") (pintype "passive"))
      (node (ref "C331") (pin "2") (pinfunction "2_2") (pintype "passive"))
      (node (ref "C332") (pin "2") (pinfunction "2_2") (pintype "passive"))
      (node (ref "C333") (pin "2") (pinfunction "2_2") (pintype "passive"))
      (node (ref "C334") (pin "2") (pinfunction "2_2") (pintype "passive"))
      (node (ref "C335") (pin "2") (pinfunction "2_2") (pintype "passive"))
      (node (ref "C336") (pin "2") (pinfunction "2_2") (pintype "passive"))
      (node (ref "C339") (pin "2") (pinfunction "2_2") (pintype "passive"))
      (node (ref "R130") (pin "1") (pinfunction "1_1") (pintype "passive"))
      (node (ref "U19") (pin "1") (pinfunction "VCC10_1") (pintype "passive"))
      (node (ref "U19") (pin "10") (pinfunction "VCC12_10") (pintype "passive"))
      (node (ref "U19") (pin "13") (pinfunction "VCC9_13") (pintype "passive"))
      (node (ref "U19") (pin "16") (pinfunction "VCC11_16") (pintype "passive"))
      (node (ref "U19") (pin "17") (pinfunction "VDDIO_17") (pintype "passive"))
      (node (ref "U19") (pin "23") (pinfunction "VCC14_23") (pintype "passive"))
      (node (ref "U19") (pin "24") (pinfunction "VCC2_24") (pintype "passive"))
      (node (ref "U19") (pin "35") (pinfunction "VLDOA_35") (pintype "passive"))
      (node (ref "U19") (pin "36") (pinfunction "VCCA_36") (pintype "passive"))
      (node (ref "U19") (pin "44") (pinfunction "VCC13_44") (pintype "passive"))
      (node (ref "U19") (pin "45") (pinfunction "VCC1_45") (pintype "passive"))
      (node (ref "U19") (pin "59") (pinfunction "VCC3_59") (pintype "passive"))
      (node (ref "U19") (pin "60") (pinfunction "VCC4_60") (pintype "passive"))
      (node (ref "U19") (pin "8") (pinfunction "VCC8_8") (pintype "passive"))
    )
    (net (code "34") (name "VCC3V_TOUCH") (class "Default")
      (node (ref "C314") (pin "2") (pinfunction "2_2") (pintype "passive"))
      (node (ref "U19") (pin "33") (pinfunction "VLDO2_33") (pintype "passive"))
    )
    (net (code "35") (name "VCCA1V8_CODEC") (class "Default")
      (node (ref "C316") (pin "2") (pinfunction "2_2") (pintype "passive"))
      (node (ref "U19") (pin "5") (pinfunction "VLDO7_5") (pintype "passive"))
    )
    (net (code "36") (name "VCCA3V_CODEC") (class "Default")
      (node (ref "C325") (pin "2") (pinfunction "2_2") (pintype "passive"))
      (node (ref "U19") (pin "14") (pinfunction "VLDO5_14") (pintype "passive"))
    )
    (net (code "37") (name "VCC_1V5") (class "Default")
      (node (ref "C326") (pin "2") (pinfunction "2_2") (pintype "passive"))
      (node (ref "U19") (pin "2") (pinfunction "VLDO6_2") (pintype "passive"))
    )
    (net (code "38") (name "VCC_1V8") (class "Default")
      (node (ref "C318") (pin "2") (pinfunction "2_2") (pintype "passive"))
      (node (ref "L8") (pin "2") (pinfunction "2_2") (pintype "passive"))
      (node (ref "R124") (pin "2") (pinfunction "2_2") (pintype "passive"))
      (node (ref "R126") (pin "2") (pinfunction "2_2") (pintype "passive"))
      (node (ref "U19") (pin "63") (pinfunction "VFB4_63") (pintype "passive"))
    )
    (net (code "39") (name "VCC_3V") (class "Default")
      (node (ref "C327") (pin "2") (pinfunction "2_2") (pintype "passive"))
      (node (ref "U19") (pin "15") (pinfunction "VLDO8_15") (pintype "passive"))
    )
    (net (code "40") (name "VCC_DDR") (class "Default")
      (node (ref "C317") (pin "2") (pinfunction "2_2") (pintype "passive"))
      (node (ref "C321") (pin "2") (pinfunction "2_2") (pintype "passive"))
      (node (ref "L10") (pin "2") (pinfunction "2_2") (pintype "passive"))
      (node (ref "Q5") (pin "3") (pinfunction "D_3") (pintype "passive"))
      (node (ref "R122") (pin "2") (pinfunction "2_2") (pintype "passive"))
    )
    (net (code "41") (name "VCC_DDRC") (class "Default")
      (node (ref "C347") (pin "2") (pinfunction "2_2") (pintype "passive"))
      (node (ref "Q5") (pin "2") (pinfunction "S_2") (pintype "passive"))
    )
    (net (code "42") (name "VCC_IN_CONN") (class "Default")
      (node (ref "R129") (pin "2") (pinfunction "2_2") (pintype "passive"))
    )
    (net (code "43") (name "VCC_RTC") (class "Default")
      (node (ref "C340") (pin "2") (pinfunction "2_2") (pintype "passive"))
      (node (ref "D5") (pin "K") (pinfunction "K_K") (pintype "passive"))
      (node (ref "U19") (pin "9") (pinfunction "VCCRTC_9") (pintype "passive"))
    )
    (net (code "44") (name "VCC_SDIO") (class "Default")
      (node (ref "C324") (pin "2") (pinfunction "2_2") (pintype "passive"))
      (node (ref "U19") (pin "12") (pinfunction "VLDO4_12") (pintype "passive"))
    )
    (net (code "45") (name "VDC_ONOFF") (class "Default")
      (node (ref "R127") (pin "2") (pinfunction "2_2") (pintype "passive"))
    )
    (net (code "46") (name "unconnected-(U19-CLK32KOUT2-Pad67)") (class "Default")
      (node (ref "U19") (pin "67") (pinfunction "CLK32KOUT2_67") (pintype "passive+no_connect"))
    )
    (net (code "47") (name "unconnected-(U19-DVSOK-Pad54)") (class "Default")
      (node (ref "U19") (pin "54") (pinfunction "DVSOK_54") (pintype "passive+no_connect"))
    )
    (net (code "48") (name "unconnected-(U19-NC1-Pad47)") (class "Default")
      (node (ref "U19") (pin "47") (pinfunction "NC1_47") (pintype "passive+no_connect"))
    )
    (net (code "49") (name "unconnected-(U19-NC2-Pad48)") (class "Default")
      (node (ref "U19") (pin "48") (pinfunction "NC2_48") (pintype "passive+no_connect"))
    )
  )
)
